# MCU.net
KiCad netlist of a schematic drawn in Altium Designer
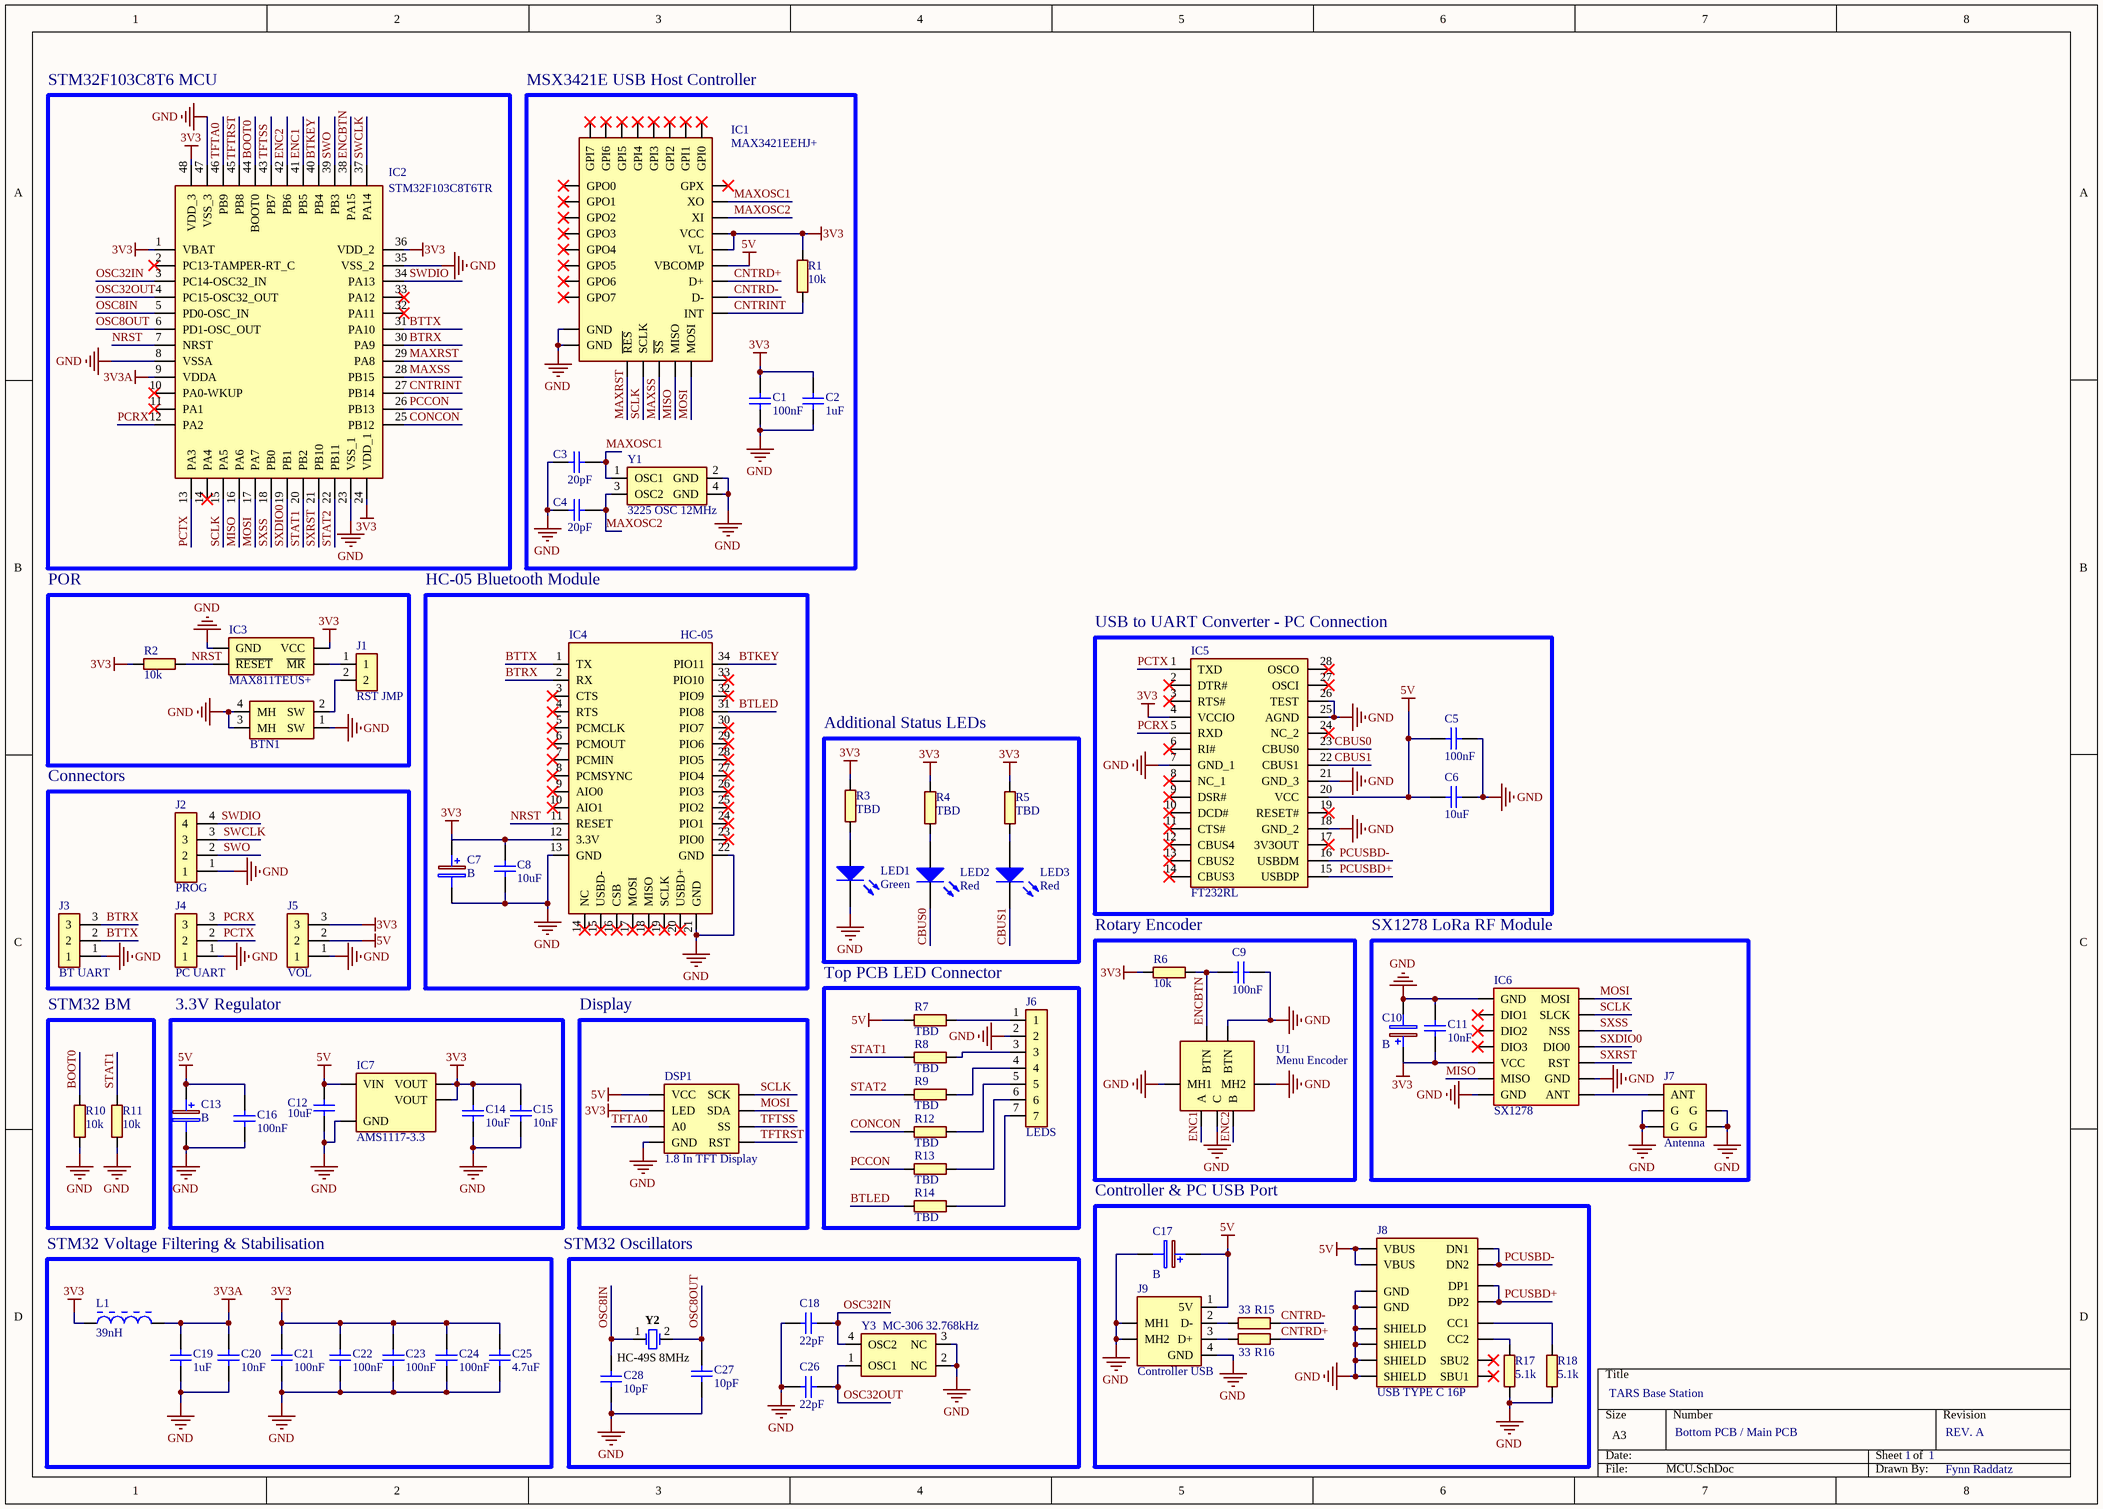
[diagram p0: MCU.SchDoc]

(export (version "E")
  (design (tool "Eeschema 10.0.6"))
  (components
    (comp (ref "BTN1")
      (value "SMD Button 6x6mm Angled")
      (footprint "SMD Button 6x6 Angled")
      (libsource (lib "SamacSys") (part "SMD Button 6x6mm Angled"))
    )
    (comp (ref "C1")
      (value "100nF")
      (footprint "SamacSys:CAPC2012 METRIC")
      (description "Capacitor")
      (fields (field (name "MANUFACTURER_PART_NUMBER") "CL21B104KACNNNC"))
      (libsource (lib "SamacSys") (part "CL21B104KACNNNC"))
    )
    (comp (ref "C2")
      (value "1uF")
      (footprint "SamacSys:CAPC2012 METRIC")
      (description "Capacitor")
      (fields (field (name "MANUFACTURER_PART_NUMBER") "CL21B104KACNNNC"))
      (libsource (lib "SamacSys") (part "CL21B104KACNNNC"))
    )
    (comp (ref "C3")
      (value "20pF")
      (footprint "SamacSys:CAPC2012 METRIC")
      (description "Capacitor")
      (fields (field (name "MANUFACTURER_PART_NUMBER") "CL21B104KACNNNC"))
      (libsource (lib "SamacSys") (part "CL21B104KACNNNC"))
    )
    (comp (ref "C4")
      (value "20pF")
      (footprint "SamacSys:CAPC2012 METRIC")
      (description "Capacitor")
      (fields (field (name "MANUFACTURER_PART_NUMBER") "CL21B104KACNNNC"))
      (libsource (lib "SamacSys") (part "CL21B104KACNNNC"))
    )
    (comp (ref "C5")
      (value "100nF")
      (footprint "SamacSys:CAPC2012 METRIC")
      (description "Capacitor")
      (fields (field (name "MANUFACTURER_PART_NUMBER") "CL21B104KACNNNC"))
      (libsource (lib "SamacSys") (part "CL21B104KACNNNC"))
    )
    (comp (ref "C6")
      (value "10uF")
      (footprint "SamacSys:CAPC2012 METRIC")
      (description "Capacitor")
      (fields (field (name "MANUFACTURER_PART_NUMBER") "CL21B104KACNNNC"))
      (libsource (lib "SamacSys") (part "CL21B104KACNNNC"))
    )
    (comp (ref "C7")
      (value "B")
      (footprint "Tantal-B-1210")
      (description "Capacitor Tantalum")
      (libsource (lib "SamacSys") (part "TANTAL-B"))
    )
    (comp (ref "C8")
      (value "10uF")
      (footprint "SamacSys:CAPC2012 METRIC")
      (description "Capacitor")
      (fields (field (name "MANUFACTURER_PART_NUMBER") "CL21B104KACNNNC"))
      (libsource (lib "SamacSys") (part "CL21B104KACNNNC"))
    )
    (comp (ref "C9")
      (value "100nF")
      (footprint "SamacSys:CAPC2012 METRIC")
      (description "Capacitor")
      (fields (field (name "MANUFACTURER_PART_NUMBER") "CL21B104KACNNNC"))
      (libsource (lib "SamacSys") (part "CL21B104KACNNNC"))
    )
    (comp (ref "C10")
      (value "B")
      (footprint "Tantal-B-1210")
      (description "Capacitor Tantalum")
      (libsource (lib "") (part "TANTAL-B_1"))
    )
    (comp (ref "C11")
      (value "10nF")
      (footprint "SamacSys:CAPC2012 METRIC")
      (description "Capacitor")
      (fields (field (name "MANUFACTURER_PART_NUMBER") "CL21B104KACNNNC"))
      (libsource (lib "SamacSys") (part "CL21B104KACNNNC"))
    )
    (comp (ref "C12")
      (value "10uF")
      (footprint "SamacSys:CAPC2012 METRIC")
      (description "Capacitor")
      (fields (field (name "MANUFACTURER_PART_NUMBER") "CL21B104KACNNNC"))
      (libsource (lib "SamacSys") (part "CL21B104KACNNNC"))
    )
    (comp (ref "C13")
      (value "B")
      (footprint "Tantal-B-1210")
      (description "Capacitor Tantalum")
      (libsource (lib "SamacSys") (part "TANTAL-B"))
    )
    (comp (ref "C14")
      (value "10uF")
      (footprint "SamacSys:CAPC2012 METRIC")
      (description "Capacitor")
      (fields (field (name "MANUFACTURER_PART_NUMBER") "CL21B104KACNNNC"))
      (libsource (lib "SamacSys") (part "CL21B104KACNNNC"))
    )
    (comp (ref "C15")
      (value "10nF")
      (footprint "SamacSys:CAPC2012 METRIC")
      (description "Capacitor")
      (fields (field (name "MANUFACTURER_PART_NUMBER") "CL21B104KACNNNC"))
      (libsource (lib "SamacSys") (part "CL21B104KACNNNC"))
    )
    (comp (ref "C16")
      (value "100nF")
      (footprint "SamacSys:CAPC2012 METRIC")
      (description "Capacitor")
      (fields (field (name "MANUFACTURER_PART_NUMBER") "CL21B104KACNNNC"))
      (libsource (lib "SamacSys") (part "CL21B104KACNNNC"))
    )
    (comp (ref "C17")
      (value "B")
      (footprint "Tantal-B-1210")
      (description "Capacitor Tantalum")
      (libsource (lib "") (part "TANTAL-B_2"))
    )
    (comp (ref "C18")
      (value "22pF")
      (footprint "SamacSys:CAPC2012 METRIC")
      (description "Capacitor")
      (fields (field (name "MANUFACTURER_PART_NUMBER") "CL21B104KACNNNC"))
      (libsource (lib "SamacSys") (part "CL21B104KACNNNC"))
    )
    (comp (ref "C19")
      (value "1uF")
      (footprint "SamacSys:CAPC2012 METRIC")
      (description "Capacitor")
      (fields (field (name "MANUFACTURER_PART_NUMBER") "CL21B104KACNNNC"))
      (libsource (lib "SamacSys") (part "CL21B104KACNNNC"))
    )
    (comp (ref "C20")
      (value "10nF")
      (footprint "SamacSys:CAPC2012 METRIC")
      (description "Capacitor")
      (fields (field (name "MANUFACTURER_PART_NUMBER") "CL21B104KACNNNC"))
      (libsource (lib "SamacSys") (part "CL21B104KACNNNC"))
    )
    (comp (ref "C21")
      (value "100nF")
      (footprint "SamacSys:CAPC2012 METRIC")
      (description "Capacitor")
      (fields (field (name "MANUFACTURER_PART_NUMBER") "CL21B104KACNNNC"))
      (libsource (lib "SamacSys") (part "CL21B104KACNNNC"))
    )
    (comp (ref "C22")
      (value "100nF")
      (footprint "SamacSys:CAPC2012 METRIC")
      (description "Capacitor")
      (fields (field (name "MANUFACTURER_PART_NUMBER") "CL21B104KACNNNC"))
      (libsource (lib "SamacSys") (part "CL21B104KACNNNC"))
    )
    (comp (ref "C23")
      (value "100nF")
      (footprint "SamacSys:CAPC2012 METRIC")
      (description "Capacitor")
      (fields (field (name "MANUFACTURER_PART_NUMBER") "CL21B104KACNNNC"))
      (libsource (lib "SamacSys") (part "CL21B104KACNNNC"))
    )
    (comp (ref "C24")
      (value "100nF")
      (footprint "SamacSys:CAPC2012 METRIC")
      (description "Capacitor")
      (fields (field (name "MANUFACTURER_PART_NUMBER") "CL21B104KACNNNC"))
      (libsource (lib "SamacSys") (part "CL21B104KACNNNC"))
    )
    (comp (ref "C25")
      (value "4.7uF")
      (footprint "SamacSys:CAPC2012 METRIC")
      (description "Capacitor")
      (fields (field (name "MANUFACTURER_PART_NUMBER") "CL21B104KACNNNC"))
      (libsource (lib "SamacSys") (part "CL21B104KACNNNC"))
    )
    (comp (ref "C26")
      (value "22pF")
      (footprint "SamacSys:CAPC2012 METRIC")
      (description "Capacitor")
      (fields (field (name "MANUFACTURER_PART_NUMBER") "CL21B104KACNNNC"))
      (libsource (lib "SamacSys") (part "CL21B104KACNNNC"))
    )
    (comp (ref "C27")
      (value "10pF")
      (footprint "SamacSys:CAPC2012 METRIC")
      (description "Capacitor")
      (fields (field (name "MANUFACTURER_PART_NUMBER") "CL21B104KACNNNC"))
      (libsource (lib "SamacSys") (part "CL21B104KACNNNC"))
    )
    (comp (ref "C28")
      (value "10pF")
      (footprint "SamacSys:CAPC2012 METRIC")
      (description "Capacitor")
      (fields (field (name "MANUFACTURER_PART_NUMBER") "CL21B104KACNNNC"))
      (libsource (lib "SamacSys") (part "CL21B104KACNNNC"))
    )
    (comp (ref "DSP1")
      (value "1.8 In TFT Display")
      (footprint "1.8 Inch TFT Display")
      (description "Display")
      (libsource (lib "SamacSys") (part "TFT Display 1.8In SPI"))
    )
    (comp (ref "IC1")
      (value "MAX3421EEHJ+")
      (footprint "SamacSys:QFP50P700X700X120-32N")
      (description "Integrated Circuit")
      (fields (field (name "MOUSER PART NUMBER") "700-MAX3421EEHJ"))
      (libsource (lib "SamacSys") (part "MAX3421EEHJ+"))
    )
    (comp (ref "IC2")
      (value "STM32F103C8T6TR")
      (footprint "SamacSys:QFP50P900X900X160-48N")
      (description "Integrated Circuit")
      (fields (field (name "MOUSER PART NUMBER") "511-STM32F103C8T6TR"))
      (libsource (lib "SamacSys") (part "STM32F103C8T6TR"))
    )
    (comp (ref "IC3")
      (value "MAX811TEUS+")
      (footprint "SamacSys:MAX811REUST")
      (description "Integrated Circuit")
      (libsource (lib "SamacSys") (part "MAX811TEUS+"))
    )
    (comp (ref "IC4") (value "HC-05") (footprint "HC-05") (libsource (lib "SamacSys") (part "HC-05")))
    (comp (ref "IC5")
      (value "FT232RL")
      (footprint "SamacSys:SOP65P778X200-28N")
      (description "Integrated Circuit")
      (libsource (lib "SamacSys") (part "FT232RL"))
    )
    (comp (ref "IC6")
      (value "SX1278")
      (footprint "SamacSys:SX1278")
      (description "RF")
      (libsource (lib "SamacSys") (part "SX1278"))
    )
    (comp (ref "IC7")
      (value "AMS1117-3.3")
      (footprint "SamacSys:SOT229P700X180-4N")
      (description "Integrated Circuit")
      (libsource (lib "SamacSys") (part "AMS1117-3.3"))
    )
    (comp (ref "J1")
      (value "RST JMP")
      (footprint "SamacSys:HDRV2W110P0X254_1X2_508X254X854P")
      (description "Connector")
      (fields
        (field (name "MANUFACTURER_PART_NUMBER") "61300211121")
        (field (name "MOUSER PART NUMBER") "710-61300211121")
      )
      (libsource (lib "SamacSys") (part "61300211121"))
    )
    (comp (ref "J2")
      (value "PROG")
      (footprint "SamacSys:HDRV4W95P0X254_1X4_1016X254X854P")
      (description "Connector")
      (fields
        (field (name "MANUFACTURER_PART_NUMBER") "61300411121")
        (field (name "MOUSER PART NUMBER") "710-61300411121")
      )
      (libsource (lib "SamacSys") (part "61300411121"))
    )
    (comp (ref "J3")
      (value "BT UART")
      (footprint "SamacSys:HDRV3W64P0X254_1X3_762X254X869P")
      (description "Connector")
      (fields
        (field (name "MANUFACTURER_PART_NUMBER") "61300311121")
        (field (name "MOUSER PART NUMBER") "710-61300311121")
      )
      (libsource (lib "SamacSys") (part "61300311121"))
    )
    (comp (ref "J4")
      (value "PC UART")
      (footprint "SamacSys:HDRV3W64P0X254_1X3_762X254X869P")
      (description "Connector")
      (fields
        (field (name "MANUFACTURER_PART_NUMBER") "61300311121")
        (field (name "MOUSER PART NUMBER") "710-61300311121")
      )
      (libsource (lib "SamacSys") (part "61300311121"))
    )
    (comp (ref "J5")
      (value "VOL")
      (footprint "SamacSys:HDRV3W64P0X254_1X3_762X254X869P")
      (description "Connector")
      (fields
        (field (name "MANUFACTURER_PART_NUMBER") "61300311121")
        (field (name "MOUSER PART NUMBER") "710-61300311121")
      )
      (libsource (lib "SamacSys") (part "61300311121"))
    )
    (comp (ref "J6")
      (value "LEDS")
      (footprint "SamacSys:HDRV7W64P0X254_1X7_1778X254X869P")
      (description "Connector")
      (fields
        (field (name "MANUFACTURER_PART_NUMBER") "61300711121")
        (field (name "MOUSER PART NUMBER") "710-61300711121")
      )
      (libsource (lib "SamacSys") (part "61300711121"))
    )
    (comp (ref "J7")
      (value "Antenna")
      (footprint "SamacSys:PCBRPSMAFRAHT")
      (description "Connector")
      (fields
        (field (name "MANUFACTURER_PART_NUMBER") "PCB.RPSMAFRA.HT")
        (field (name "MOUSER PART NUMBER") "960-PCB.RPSMAFRA.HT")
      )
      (libsource (lib "SamacSys") (part "PCB.RPSMAFRA.HT"))
    )
    (comp (ref "J8")
      (value "USB TYPE C 16P")
      (footprint "USB TYPE C 16P")
      (libsource (lib "SamacSys") (part "USB TYPE C 16P"))
    )
    (comp (ref "J9")
      (value "Controller USB")
      (footprint "SamacSys:875200010BLF")
      (description "Connector")
      (fields
        (field (name "MANUFACTURER_PART_NUMBER") "87520-0010BLF")
        (field (name "MOUSER PART NUMBER") "649-87520-0010BLF")
      )
      (libsource (lib "SamacSys") (part "87520-0010BLF"))
    )
    (comp (ref "L1")
      (value "39nH")
      (footprint "LIRD-LI0805H151R-10-2_V")
      (description "Chip Bead, 100 MHz, 5 A, -40 to 125 degC, 2-Pin SMD (0805), RoHS, Tape and Reel")
      (fields (field (name "MANUFACTURER") "Laird"))
      (libsource (lib "Altium Content Vault") (part "IND-FB-2"))
    )
    (comp (ref "LED1")
      (value "Green")
      (footprint "1206_A")
      (description "SMD mono-color Chip LED, WL-SMCW, Green")
      (fields (field (name "MANUFACTURER") "Wuerth Elektronik") (field (name "PARTNUMBER") "150120GS75000"))
      (libsource (lib "Altium Content Vault") (part "WE-LED_K1A2-2"))
    )
    (comp (ref "LED2")
      (value "Red")
      (footprint "1206_A")
      (description "SMD mono-color Chip LED, WL-SMCW, Green")
      (fields (field (name "MANUFACTURER") "Wuerth Elektronik") (field (name "PARTNUMBER") "150120GS75000"))
      (libsource (lib "Altium Content Vault") (part "WE-LED_K1A2-2"))
    )
    (comp (ref "LED3")
      (value "Red")
      (footprint "1206_A")
      (description "SMD mono-color Chip LED, WL-SMCW, Green")
      (fields (field (name "MANUFACTURER") "Wuerth Elektronik") (field (name "PARTNUMBER") "150120GS75000"))
      (libsource (lib "Altium Content Vault") (part "WE-LED_K1A2-2"))
    )
    (comp (ref "R1")
      (value "10k")
      (footprint "SamacSys:RESC2012X65N")
      (description "Resistor")
      (fields (field (name "MANUFACTURER_PART_NUMBER") "RMCF0805ZT0R00"))
      (libsource (lib "SamacSys") (part "Res 0805"))
    )
    (comp (ref "R2")
      (value "10k")
      (footprint "SamacSys:RESC2012X65N")
      (description "Resistor")
      (fields (field (name "MANUFACTURER_PART_NUMBER") "RMCF0805ZT0R00"))
      (libsource (lib "") (part "Res 0805_1"))
    )
    (comp (ref "R3")
      (value "TBD")
      (footprint "SamacSys:RESC2012X65N")
      (description "Resistor")
      (fields (field (name "MANUFACTURER_PART_NUMBER") "RMCF0805ZT0R00"))
      (libsource (lib "SamacSys") (part "Res 0805"))
    )
    (comp (ref "R4")
      (value "TBD")
      (footprint "SamacSys:RESC2012X65N")
      (description "Resistor")
      (fields (field (name "MANUFACTURER_PART_NUMBER") "RMCF0805ZT0R00"))
      (libsource (lib "SamacSys") (part "Res 0805"))
    )
    (comp (ref "R5")
      (value "TBD")
      (footprint "SamacSys:RESC2012X65N")
      (description "Resistor")
      (fields (field (name "MANUFACTURER_PART_NUMBER") "RMCF0805ZT0R00"))
      (libsource (lib "SamacSys") (part "Res 0805"))
    )
    (comp (ref "R6")
      (value "10k")
      (footprint "SamacSys:RESC2012X65N")
      (description "Resistor")
      (fields (field (name "MANUFACTURER_PART_NUMBER") "RMCF0805ZT0R00"))
      (libsource (lib "") (part "Res 0805_1"))
    )
    (comp (ref "R7")
      (value "TBD")
      (footprint "SamacSys:RESC2012X65N")
      (description "Resistor")
      (fields (field (name "MANUFACTURER_PART_NUMBER") "RMCF0805ZT0R00"))
      (libsource (lib "") (part "Res 0805_1"))
    )
    (comp (ref "R8")
      (value "TBD")
      (footprint "SamacSys:RESC2012X65N")
      (description "Resistor")
      (fields (field (name "MANUFACTURER_PART_NUMBER") "RMCF0805ZT0R00"))
      (libsource (lib "") (part "Res 0805_1"))
    )
    (comp (ref "R9")
      (value "TBD")
      (footprint "SamacSys:RESC2012X65N")
      (description "Resistor")
      (fields (field (name "MANUFACTURER_PART_NUMBER") "RMCF0805ZT0R00"))
      (libsource (lib "") (part "Res 0805_1"))
    )
    (comp (ref "R10")
      (value "10k")
      (footprint "SamacSys:RESC2012X65N")
      (description "Resistor")
      (fields (field (name "MANUFACTURER_PART_NUMBER") "RMCF0805ZT0R00"))
      (libsource (lib "") (part "Res 0805_3"))
    )
    (comp (ref "R11")
      (value "10k")
      (footprint "SamacSys:RESC2012X65N")
      (description "Resistor")
      (fields (field (name "MANUFACTURER_PART_NUMBER") "RMCF0805ZT0R00"))
      (libsource (lib "") (part "Res 0805_3"))
    )
    (comp (ref "R12")
      (value "TBD")
      (footprint "SamacSys:RESC2012X65N")
      (description "Resistor")
      (fields (field (name "MANUFACTURER_PART_NUMBER") "RMCF0805ZT0R00"))
      (libsource (lib "") (part "Res 0805_1"))
    )
    (comp (ref "R13")
      (value "TBD")
      (footprint "SamacSys:RESC2012X65N")
      (description "Resistor")
      (fields (field (name "MANUFACTURER_PART_NUMBER") "RMCF0805ZT0R00"))
      (libsource (lib "") (part "Res 0805_1"))
    )
    (comp (ref "R14")
      (value "TBD")
      (footprint "SamacSys:RESC2012X65N")
      (description "Resistor")
      (fields (field (name "MANUFACTURER_PART_NUMBER") "RMCF0805ZT0R00"))
      (libsource (lib "") (part "Res 0805_1"))
    )
    (comp (ref "R15")
      (value "33")
      (footprint "SamacSys:RESC2012X65N")
      (description "Resistor")
      (fields (field (name "MANUFACTURER_PART_NUMBER") "RMCF0805ZT0R00"))
      (libsource (lib "") (part "Res 0805_2"))
    )
    (comp (ref "R16")
      (value "33")
      (footprint "SamacSys:RESC2012X65N")
      (description "Resistor")
      (fields (field (name "MANUFACTURER_PART_NUMBER") "RMCF0805ZT0R00"))
      (libsource (lib "") (part "Res 0805_2"))
    )
    (comp (ref "R17")
      (value "5.1k")
      (footprint "SamacSys:RESC2012X65N")
      (description "Resistor")
      (fields (field (name "MANUFACTURER_PART_NUMBER") "RMCF0805ZT0R00"))
      (libsource (lib "SamacSys") (part "Res 0805"))
    )
    (comp (ref "R18")
      (value "5.1k")
      (footprint "SamacSys:RESC2012X65N")
      (description "Resistor")
      (fields (field (name "MANUFACTURER_PART_NUMBER") "RMCF0805ZT0R00"))
      (libsource (lib "SamacSys") (part "Res 0805"))
    )
    (comp (ref "U1")
      (value "Menu Encoder")
      (footprint "SamacSys:EC11B152442D")
      (description "Encoder")
      (fields (field (name "MANUFACTURER_PART_NUMBER") "EC11B152442D"))
      (libsource (lib "SamacSys") (part "EC11B152442D"))
    )
    (comp (ref "Y1")
      (value "3225 OSC 12MHz")
      (footprint "SamacSys:TSX3225240000MF20GAC0")
      (description "Crystal or Oscillator")
      (fields
        (field (name "MANUFACTURER_PART_NUMBER") "TSX-3225 16.0000MF10U-B0")
        (field (name "MOUSER PART NUMBER") "732-322516MF10U-B0")
      )
      (libsource (lib "SamacSys") (part "TSX-3225_16.0000MF10U-B0"))
    )
    (comp (ref "Y2")
      (value "HC-49S 8MHz")
      (footprint "FOX-HC49SDLF_V")
      (description "Resistance Weld Crystal, 8 MHz, +/- 30 ppm, -20 to 70 degC, 2-Pin SMD, RoHS, Tape and Reel")
      (fields (field (name "MANUFACTURER") "FOX Electronics") (field (name "TOLERANCE") "50ppm"))
      (libsource (lib "Altium Content Vault") (part "XTAL-1-2-2"))
    )
    (comp (ref "Y3")
      (value "MC-306 32.768kHz")
      (footprint "SamacSys:MC306327680KA3ROHS")
      (description "Crystal or Oscillator")
      (fields
        (field (name "MANUFACTURER_PART_NUMBER") "MC-306 32.7680K-A3:ROHS")
        (field (name "MOUSER PART NUMBER") "732-MC306-32.7KA3R")
      )
      (libsource (lib "SamacSys") (part "MC-306_32.7680K-A3_ROHS"))
    )
  )
  (nets
    (net (code "1") (name "/BOOT0") (class "Default")
      (node (ref "IC2") (pin "44") (pinfunction "BOOT0_44") (pintype "passive"))
      (node (ref "R10") (pin "1") (pinfunction "1_1") (pintype "passive"))
    )
    (net (code "2") (name "/BTKEY") (class "Default")
      (node (ref "IC2") (pin "40") (pinfunction "PB4_40") (pintype "passive"))
      (node (ref "IC4") (pin "34") (pinfunction "PIO11_34") (pintype "passive"))
    )
    (net (code "3") (name "/BTLED") (class "Default")
      (node (ref "IC4") (pin "31") (pinfunction "PIO8_31") (pintype "passive"))
      (node (ref "R14") (pin "2") (pinfunction "2_2") (pintype "passive"))
    )
    (net (code "4") (name "/BTRX") (class "Default")
      (node (ref "IC2") (pin "30") (pinfunction "PA9_30") (pintype "passive"))
      (node (ref "IC4") (pin "2") (pinfunction "RX_2") (pintype "passive"))
      (node (ref "J3") (pin "3") (pinfunction "3_3") (pintype "passive"))
    )
    (net (code "5") (name "/BTTX") (class "Default")
      (node (ref "IC2") (pin "31") (pinfunction "PA10_31") (pintype "passive"))
      (node (ref "IC4") (pin "1") (pinfunction "TX_1") (pintype "passive"))
      (node (ref "J3") (pin "2") (pinfunction "2_2") (pintype "passive"))
    )
    (net (code "6") (name "/CBUS0") (class "Default")
      (node (ref "IC5") (pin "23") (pinfunction "CBUS0_23") (pintype "passive"))
      (node (ref "LED2") (pin "1") (pinfunction "K_1") (pintype "passive"))
    )
    (net (code "7") (name "/CBUS1") (class "Default")
      (node (ref "IC5") (pin "22") (pinfunction "CBUS1_22") (pintype "passive"))
      (node (ref "LED3") (pin "1") (pinfunction "K_1") (pintype "passive"))
    )
    (net (code "8") (name "/CNTRD+") (class "Default")
      (node (ref "IC1") (pin "21") (pinfunction "D+_21") (pintype "passive"))
      (node (ref "R16") (pin "2") (pinfunction "2_2") (pintype "passive"))
    )
    (net (code "9") (name "/CNTRD-") (class "Default")
      (node (ref "IC1") (pin "20") (pinfunction "D-_20") (pintype "passive"))
      (node (ref "R15") (pin "2") (pinfunction "2_2") (pintype "passive"))
    )
    (net (code "10") (name "/CNTRINT") (class "Default")
      (node (ref "IC1") (pin "18") (pinfunction "INT_18") (pintype "passive"))
      (node (ref "IC2") (pin "27") (pinfunction "PB14_27") (pintype "passive"))
      (node (ref "R1") (pin "1") (pinfunction "1_1") (pintype "passive"))
    )
    (net (code "11") (name "/CONCON") (class "Default")
      (node (ref "IC2") (pin "25") (pinfunction "PB12_25") (pintype "passive"))
      (node (ref "R12") (pin "2") (pinfunction "2_2") (pintype "passive"))
    )
    (net (code "12") (name "/ENC1") (class "Default")
      (node (ref "IC2") (pin "41") (pinfunction "PB5_41") (pintype "passive"))
      (node (ref "U1") (pin "A") (pinfunction "A_A") (pintype "passive"))
    )
    (net (code "13") (name "/ENC2") (class "Default")
      (node (ref "IC2") (pin "42") (pinfunction "PB6_42") (pintype "passive"))
      (node (ref "U1") (pin "B") (pinfunction "B_B") (pintype "passive"))
    )
    (net (code "14") (name "/ENCBTN") (class "Default")
      (node (ref "C9") (pin "1") (pinfunction "1_1") (pintype "passive"))
      (node (ref "IC2") (pin "38") (pinfunction "PA15_38") (pintype "passive"))
      (node (ref "R6") (pin "1") (pinfunction "1_1") (pintype "passive"))
      (node (ref "U1") (pin "MH3") (pinfunction "BTN_MH3") (pintype "passive"))
    )
    (net (code "15") (name "/MAXOSC1") (class "Default")
      (node (ref "C3") (pin "1") (pinfunction "1_1") (pintype "passive"))
      (node (ref "IC1") (pin "25") (pinfunction "XO_25") (pintype "passive"))
      (node (ref "Y1") (pin "1") (pinfunction "OSC1_1") (pintype "passive"))
    )
    (net (code "16") (name "/MAXOSC2") (class "Default")
      (node (ref "C4") (pin "1") (pinfunction "1_1") (pintype "passive"))
      (node (ref "IC1") (pin "24") (pinfunction "XI_24") (pintype "passive"))
      (node (ref "Y1") (pin "3") (pinfunction "OSC2_3") (pintype "passive"))
    )
    (net (code "17") (name "/MAXRST") (class "Default")
      (node (ref "IC1") (pin "12") (pinfunction "~{RES}_12") (pintype "passive"))
      (node (ref "IC2") (pin "29") (pinfunction "PA8_29") (pintype "passive"))
    )
    (net (code "18") (name "/MAXSS") (class "Default")
      (node (ref "IC1") (pin "14") (pinfunction "~{SS}_14") (pintype "passive"))
      (node (ref "IC2") (pin "28") (pinfunction "PB15_28") (pintype "passive"))
    )
    (net (code "19") (name "/MISO") (class "Default")
      (node (ref "IC1") (pin "15") (pinfunction "MISO_15") (pintype "passive"))
      (node (ref "IC2") (pin "16") (pinfunction "PA6_16") (pintype "passive"))
      (node (ref "IC6") (pin "6") (pinfunction "MISO_6") (pintype "passive"))
    )
    (net (code "20") (name "/MOSI") (class "Default")
      (node (ref "DSP1") (pin "3") (pinfunction "SDA_3") (pintype "passive"))
      (node (ref "IC1") (pin "16") (pinfunction "MOSI_16") (pintype "passive"))
      (node (ref "IC2") (pin "17") (pinfunction "PA7_17") (pintype "passive"))
      (node (ref "IC6") (pin "7") (pinfunction "MOSI_7") (pintype "passive"))
    )
    (net (code "21") (name "/NRST") (class "Default")
      (node (ref "IC2") (pin "7") (pinfunction "NRST_7") (pintype "passive"))
      (node (ref "IC3") (pin "2") (pinfunction "~{RESET}_2") (pintype "passive"))
      (node (ref "IC4") (pin "11") (pinfunction "RESET_11") (pintype "passive"))
      (node (ref "R2") (pin "1") (pinfunction "1_1") (pintype "passive"))
    )
    (net (code "22") (name "/OSC8IN") (class "Default")
      (node (ref "C28") (pin "2") (pinfunction "2_2") (pintype "passive"))
      (node (ref "IC2") (pin "5") (pinfunction "PD0-OSC_IN_5") (pintype "passive"))
      (node (ref "Y2") (pin "1") (pinfunction "1_1") (pintype "passive"))
    )
    (net (code "23") (name "/OSC8OUT") (class "Default")
      (node (ref "C27") (pin "2") (pinfunction "2_2") (pintype "passive"))
      (node (ref "IC2") (pin "6") (pinfunction "PD1-OSC_OUT_6") (pintype "passive"))
      (node (ref "Y2") (pin "2") (pinfunction "2_2") (pintype "passive"))
    )
    (net (code "24") (name "/OSC32IN") (class "Default")
      (node (ref "C18") (pin "1") (pinfunction "1_1") (pintype "passive"))
      (node (ref "IC2") (pin "3") (pinfunction "PC14-OSC32_IN_3") (pintype "passive"))
      (node (ref "Y3") (pin "4") (pinfunction "OSC2_4") (pintype "passive"))
    )
    (net (code "25") (name "/OSC32OUT") (class "Default")
      (node (ref "C26") (pin "1") (pinfunction "1_1") (pintype "passive"))
      (node (ref "IC2") (pin "4") (pinfunction "PC15-OSC32_OUT_4") (pintype "passive"))
      (node (ref "Y3") (pin "1") (pinfunction "OSC1_1") (pintype "passive"))
    )
    (net (code "26") (name "/PCCON") (class "Default")
      (node (ref "IC2") (pin "26") (pinfunction "PB13_26") (pintype "passive"))
      (node (ref "R13") (pin "2") (pinfunction "2_2") (pintype "passive"))
    )
    (net (code "27") (name "/PCRX") (class "Default")
      (node (ref "IC2") (pin "12") (pinfunction "PA2_12") (pintype "passive"))
      (node (ref "IC5") (pin "5") (pinfunction "RXD_5") (pintype "passive"))
      (node (ref "J4") (pin "3") (pinfunction "3_3") (pintype "passive"))
    )
    (net (code "28") (name "/PCTX") (class "Default")
      (node (ref "IC2") (pin "13") (pinfunction "PA3_13") (pintype "passive"))
      (node (ref "IC5") (pin "1") (pinfunction "TXD_1") (pintype "passive"))
      (node (ref "J4") (pin "2") (pinfunction "2_2") (pintype "passive"))
    )
    (net (code "29") (name "/PCUSBD+") (class "Default")
      (node (ref "IC5") (pin "15") (pinfunction "USBDP_15") (pintype "passive"))
      (node (ref "J8") (pin "A6") (pinfunction "DP1_A6") (pintype "passive"))
      (node (ref "J8") (pin "B6") (pinfunction "DP2_B6") (pintype "passive"))
    )
    (net (code "30") (name "/PCUSBD-") (class "Default")
      (node (ref "IC5") (pin "16") (pinfunction "USBDM_16") (pintype "passive"))
      (node (ref "J8") (pin "A7") (pinfunction "DN1_A7") (pintype "passive"))
      (node (ref "J8") (pin "B7") (pinfunction "DN2_B7") (pintype "passive"))
    )
    (net (code "31") (name "/SCLK") (class "Default")
      (node (ref "DSP1") (pin "2") (pinfunction "SCK_2") (pintype "passive"))
      (node (ref "IC1") (pin "13") (pinfunction "SCLK_13") (pintype "passive"))
      (node (ref "IC2") (pin "15") (pinfunction "PA5_15") (pintype "passive"))
      (node (ref "IC6") (pin "8") (pinfunction "SLCK_8") (pintype "passive"))
    )
    (net (code "32") (name "/STAT1") (class "Default")
      (node (ref "IC2") (pin "20") (pinfunction "PB2_20") (pintype "passive"))
      (node (ref "R11") (pin "1") (pinfunction "1_1") (pintype "passive"))
      (node (ref "R8") (pin "2") (pinfunction "2_2") (pintype "passive"))
    )
    (net (code "33") (name "/STAT2") (class "Default")
      (node (ref "IC2") (pin "22") (pinfunction "PB11_22") (pintype "passive"))
      (node (ref "R9") (pin "2") (pinfunction "2_2") (pintype "passive"))
    )
    (net (code "34") (name "/SWCLK") (class "Default")
      (node (ref "IC2") (pin "37") (pinfunction "PA14_37") (pintype "passive"))
      (node (ref "J2") (pin "3") (pinfunction "3_3") (pintype "passive"))
    )
    (net (code "35") (name "/SWDIO") (class "Default")
      (node (ref "IC2") (pin "34") (pinfunction "PA13_34") (pintype "passive"))
      (node (ref "J2") (pin "4") (pinfunction "4_4") (pintype "passive"))
    )
    (net (code "36") (name "/SWO") (class "Default")
      (node (ref "IC2") (pin "39") (pinfunction "PB3_39") (pintype "passive"))
      (node (ref "J2") (pin "2") (pinfunction "2_2") (pintype "passive"))
    )
    (net (code "37") (name "/SXDIO0") (class "Default")
      (node (ref "IC2") (pin "19") (pinfunction "PB1_19") (pintype "passive"))
      (node (ref "IC6") (pin "10") (pinfunction "DIO0_10") (pintype "passive"))
    )
    (net (code "38") (name "/SXRST") (class "Default")
      (node (ref "IC2") (pin "21") (pinfunction "PB10_21") (pintype "passive"))
      (node (ref "IC6") (pin "11") (pinfunction "RST_11") (pintype "passive"))
    )
    (net (code "39") (name "/SXSS") (class "Default")
      (node (ref "IC2") (pin "18") (pinfunction "PB0_18") (pintype "passive"))
      (node (ref "IC6") (pin "9") (pinfunction "NSS_9") (pintype "passive"))
    )
    (net (code "40") (name "/TFTA0") (class "Default")
      (node (ref "DSP1") (pin "4") (pinfunction "A0_4") (pintype "passive"))
      (node (ref "IC2") (pin "46") (pinfunction "PB9_46") (pintype "passive"))
    )
    (net (code "41") (name "/TFTRST") (class "Default")
      (node (ref "DSP1") (pin "5") (pinfunction "RST_5") (pintype "passive"))
      (node (ref "IC2") (pin "45") (pinfunction "PB8_45") (pintype "passive"))
    )
    (net (code "42") (name "/TFTSS") (class "Default")
      (node (ref "DSP1") (pin "6") (pinfunction "SS_6") (pintype "passive"))
      (node (ref "IC2") (pin "43") (pinfunction "PB7_43") (pintype "passive"))
    )
    (net (code "43") (name "3V3") (class "Default")
      (node (ref "C1") (pin "1") (pinfunction "1_1") (pintype "passive"))
      (node (ref "C10") (pin "1") (pinfunction "+_1") (pintype "passive"))
      (node (ref "C11") (pin "2") (pinfunction "2_2") (pintype "passive"))
      (node (ref "C14") (pin "1") (pinfunction "1_1") (pintype "passive"))
      (node (ref "C15") (pin "1") (pinfunction "1_1") (pintype "passive"))
      (node (ref "C2") (pin "1") (pinfunction "1_1") (pintype "passive"))
      (node (ref "C21") (pin "2") (pinfunction "2_2") (pintype "passive"))
      (node (ref "C22") (pin "2") (pinfunction "2_2") (pintype "passive"))
      (node (ref "C23") (pin "2") (pinfunction "2_2") (pintype "passive"))
      (node (ref "C24") (pin "2") (pinfunction "2_2") (pintype "passive"))
      (node (ref "C25") (pin "2") (pinfunction "2_2") (pintype "passive"))
      (node (ref "C7") (pin "1") (pinfunction "+_1") (pintype "passive"))
      (node (ref "C8") (pin "1") (pinfunction "1_1") (pintype "passive"))
      (node (ref "DSP1") (pin "1") (pinfunction "LED_1") (pintype "passive"))
      (node (ref "IC1") (pin "2") (pinfunction "VL_2") (pintype "passive"))
      (node (ref "IC1") (pin "23") (pinfunction "VCC_23") (pintype "passive"))
      (node (ref "IC2") (pin "1") (pinfunction "VBAT_1") (pintype "passive"))
      (node (ref "IC2") (pin "24") (pinfunction "VDD_1_24") (pintype "passive"))
      (node (ref "IC2") (pin "36") (pinfunction "VDD_2_36") (pintype "passive"))
      (node (ref "IC2") (pin "48") (pinfunction "VDD_3_48") (pintype "passive"))
      (node (ref "IC3") (pin "4") (pinfunction "VCC_4") (pintype "passive"))
      (node (ref "IC4") (pin "12") (pinfunction "3.3V_12") (pintype "passive"))
      (node (ref "IC5") (pin "4") (pinfunction "VCCIO_4") (pintype "passive"))
      (node (ref "IC6") (pin "5") (pinfunction "VCC_5") (pintype "passive"))
      (node (ref "IC7") (pin "2") (pinfunction "VOUT_2") (pintype "passive"))
      (node (ref "IC7") (pin "4") (pinfunction "VOUT_4") (pintype "passive"))
      (node (ref "J5") (pin "3") (pinfunction "3_3") (pintype "passive"))
      (node (ref "L1") (pin "1") (pinfunction "1_1") (pintype "passive"))
      (node (ref "R1") (pin "2") (pinfunction "2_2") (pintype "passive"))
      (node (ref "R2") (pin "2") (pinfunction "2_2") (pintype "passive"))
      (node (ref "R3") (pin "2") (pinfunction "2_2") (pintype "passive"))
      (node (ref "R4") (pin "2") (pinfunction "2_2") (pintype "passive"))
      (node (ref "R5") (pin "2") (pinfunction "2_2") (pintype "passive"))
      (node (ref "R6") (pin "2") (pinfunction "2_2") (pintype "passive"))
    )
    (net (code "44") (name "3V3A") (class "Default")
      (node (ref "C19") (pin "2") (pinfunction "2_2") (pintype "passive"))
      (node (ref "C20") (pin "2") (pinfunction "2_2") (pintype "passive"))
      (node (ref "IC2") (pin "9") (pinfunction "VDDA_9") (pintype "passive"))
      (node (ref "L1") (pin "2") (pinfunction "2_2") (pintype "passive"))
    )
    (net (code "45") (name "5V") (class "Default")
      (node (ref "C12") (pin "1") (pinfunction "1_1") (pintype "passive"))
      (node (ref "C13") (pin "1") (pinfunction "+_1") (pintype "passive"))
      (node (ref "C16") (pin "2") (pinfunction "2_2") (pintype "passive"))
      (node (ref "C17") (pin "1") (pinfunction "+_1") (pintype "passive"))
      (node (ref "C5") (pin "1") (pinfunction "1_1") (pintype "passive"))
      (node (ref "C6") (pin "1") (pinfunction "1_1") (pintype "passive"))
      (node (ref "DSP1") (pin "8") (pinfunction "VCC_8") (pintype "passive"))
      (node (ref "IC1") (pin "22") (pinfunction "VBCOMP_22") (pintype "passive"))
      (node (ref "IC5") (pin "20") (pinfunction "VCC_20") (pintype "passive"))
      (node (ref "IC7") (pin "3") (pinfunction "VIN_3") (pintype "passive"))
      (node (ref "J5") (pin "2") (pinfunction "2_2") (pintype "passive"))
      (node (ref "J8") (pin "A4B9") (pinfunction "VBUS_A4B9") (pintype "power_in"))
      (node (ref "J8") (pin "B4A9") (pinfunction "VBUS_B4A9") (pintype "power_in"))
      (node (ref "J9") (pin "1") (pinfunction "5V_1") (pintype "passive"))
      (node (ref "R7") (pin "2") (pinfunction "2_2") (pintype "passive"))
    )
    (net (code "46") (name "GND") (class "Default")
      (node (ref "BTN1") (pin "1") (pinfunction "SW_1") (pintype "passive"))
      (node (ref "BTN1") (pin "3") (pinfunction "MH_3") (pintype "passive"))
      (node (ref "BTN1") (pin "4") (pinfunction "MH_4") (pintype "passive"))
      (node (ref "C1") (pin "2") (pinfunction "2_2") (pintype "passive"))
      (node (ref "C10") (pin "2") (pinfunction "-_2") (pintype "passive"))
      (node (ref "C11") (pin "1") (pinfunction "1_1") (pintype "passive"))
      (node (ref "C12") (pin "2") (pinfunction "2_2") (pintype "passive"))
      (node (ref "C13") (pin "2") (pinfunction "-_2") (pintype "passive"))
      (node (ref "C14") (pin "2") (pinfunction "2_2") (pintype "passive"))
      (node (ref "C15") (pin "2") (pinfunction "2_2") (pintype "passive"))
      (node (ref "C16") (pin "1") (pinfunction "1_1") (pintype "passive"))
      (node (ref "C17") (pin "2") (pinfunction "-_2") (pintype "passive"))
      (node (ref "C18") (pin "2") (pinfunction "2_2") (pintype "passive"))
      (node (ref "C19") (pin "1") (pinfunction "1_1") (pintype "passive"))
      (node (ref "C2") (pin "2") (pinfunction "2_2") (pintype "passive"))
      (node (ref "C20") (pin "1") (pinfunction "1_1") (pintype "passive"))
      (node (ref "C21") (pin "1") (pinfunction "1_1") (pintype "passive"))
      (node (ref "C22") (pin "1") (pinfunction "1_1") (pintype "passive"))
      (node (ref "C23") (pin "1") (pinfunction "1_1") (pintype "passive"))
      (node (ref "C24") (pin "1") (pinfunction "1_1") (pintype "passive"))
      (node (ref "C25") (pin "1") (pinfunction "1_1") (pintype "passive"))
      (node (ref "C26") (pin "2") (pinfunction "2_2") (pintype "passive"))
      (node (ref "C27") (pin "1") (pinfunction "1_1") (pintype "passive"))
      (node (ref "C28") (pin "1") (pinfunction "1_1") (pintype "passive"))
      (node (ref "C3") (pin "2") (pinfunction "2_2") (pintype "passive"))
      (node (ref "C4") (pin "2") (pinfunction "2_2") (pintype "passive"))
      (node (ref "C5") (pin "2") (pinfunction "2_2") (pintype "passive"))
      (node (ref "C6") (pin "2") (pinfunction "2_2") (pintype "passive"))
      (node (ref "C7") (pin "2") (pinfunction "-_2") (pintype "passive"))
      (node (ref "C8") (pin "2") (pinfunction "2_2") (pintype "passive"))
      (node (ref "C9") (pin "2") (pinfunction "2_2") (pintype "passive"))
      (node (ref "DSP1") (pin "7") (pinfunction "GND_7") (pintype "passive"))
      (node (ref "IC1") (pin "19") (pinfunction "GND_19") (pintype "passive"))
      (node (ref "IC1") (pin "3") (pinfunction "GND_3") (pintype "passive"))
      (node (ref "IC2") (pin "23") (pinfunction "VSS_1_23") (pintype "passive"))
      (node (ref "IC2") (pin "35") (pinfunction "VSS_2_35") (pintype "passive"))
      (node (ref "IC2") (pin "47") (pinfunction "VSS_3_47") (pintype "passive"))
      (node (ref "IC2") (pin "8") (pinfunction "VSSA_8") (pintype "passive"))
      (node (ref "IC3") (pin "1") (pinfunction "GND_1") (pintype "passive"))
      (node (ref "IC4") (pin "13") (pinfunction "GND_13") (pintype "passive"))
      (node (ref "IC4") (pin "21") (pinfunction "GND_21") (pintype "passive"))
      (node (ref "IC4") (pin "22") (pinfunction "GND_22") (pintype "passive"))
      (node (ref "IC5") (pin "18") (pinfunction "GND_2_18") (pintype "passive"))
      (node (ref "IC5") (pin "21") (pinfunction "GND_3_21") (pintype "passive"))
      (node (ref "IC5") (pin "25") (pinfunction "AGND_25") (pintype "passive"))
      (node (ref "IC5") (pin "26") (pinfunction "TEST_26") (pintype "passive"))
      (node (ref "IC5") (pin "7") (pinfunction "GND_1_7") (pintype "passive"))
      (node (ref "IC6") (pin "1") (pinfunction "GND_1") (pintype "passive"))
      (node (ref "IC6") (pin "12") (pinfunction "GND_12") (pintype "passive"))
      (node (ref "IC6") (pin "14") (pinfunction "GND_14") (pintype "passive"))
      (node (ref "IC7") (pin "1") (pinfunction "GND_1") (pintype "passive"))
      (node (ref "J2") (pin "1") (pinfunction "1_1") (pintype "passive"))
      (node (ref "J3") (pin "1") (pinfunction "1_1") (pintype "passive"))
      (node (ref "J4") (pin "1") (pinfunction "1_1") (pintype "passive"))
      (node (ref "J5") (pin "1") (pinfunction "1_1") (pintype "passive"))
      (node (ref "J6") (pin "2") (pinfunction "2_2") (pintype "passive"))
      (node (ref "J7") (pin "2") (pinfunction "G_2") (pintype "passive"))
      (node (ref "J7") (pin "3") (pinfunction "G_3") (pintype "passive"))
      (node (ref "J7") (pin "4") (pinfunction "G_4") (pintype "passive"))
      (node (ref "J7") (pin "5") (pinfunction "G_5") (pintype "passive"))
      (node (ref "J8") (pin "A1B12") (pinfunction "GND_A1B12") (pintype "power_in"))
      (node (ref "J8") (pin "B1A12") (pinfunction "GND_B1A12") (pintype "power_in"))
      (node (ref "J8") (pin "S1") (pinfunction "SHIELD_S1") (pintype "passive"))
      (node (ref "J8") (pin "S2") (pinfunction "SHIELD_S2") (pintype "passive"))
      (node (ref "J8") (pin "S3") (pinfunction "SHIELD_S3") (pintype "passive"))
      (node (ref "J8") (pin "S4") (pinfunction "SHIELD_S4") (pintype "passive"))
      (node (ref "J9") (pin "4") (pinfunction "GND_4") (pintype "passive"))
      (node (ref "J9") (pin "MH1") (pinfunction "MH1_MH1") (pintype "passive"))
      (node (ref "J9") (pin "MH2") (pinfunction "MH2_MH2") (pintype "passive"))
      (node (ref "LED1") (pin "1") (pinfunction "K_1") (pintype "passive"))
      (node (ref "R10") (pin "2") (pinfunction "2_2") (pintype "passive"))
      (node (ref "R11") (pin "2") (pinfunction "2_2") (pintype "passive"))
      (node (ref "R17") (pin "1") (pinfunction "1_1") (pintype "passive"))
      (node (ref "R18") (pin "1") (pinfunction "1_1") (pintype "passive"))
      (node (ref "U1") (pin "C") (pinfunction "C_C") (pintype "passive"))
      (node (ref "U1") (pin "MH1") (pinfunction "MH1_MH1") (pintype "passive"))
      (node (ref "U1") (pin "MH2") (pinfunction "MH2_MH2") (pintype "passive"))
      (node (ref "U1") (pin "MH4") (pinfunction "BTN_MH4") (pintype "passive"))
      (node (ref "Y1") (pin "2") (pinfunction "GND_2") (pintype "passive"))
      (node (ref "Y1") (pin "4") (pinfunction "GND_4") (pintype "passive"))
      (node (ref "Y3") (pin "2") (pinfunction "NC_2") (pintype "passive"))
      (node (ref "Y3") (pin "3") (pinfunction "NC_3") (pintype "passive"))
    )
    (net (code "47") (name "Net-(BTN1-SW-Pad2)") (class "Default")
      (node (ref "BTN1") (pin "2") (pinfunction "SW_2") (pintype "passive"))
      (node (ref "J1") (pin "2") (pinfunction "2_2") (pintype "passive"))
    )
    (net (code "48") (name "Net-(IC3-~{MR})") (class "Default")
      (node (ref "IC3") (pin "3") (pinfunction "~{MR}_3") (pintype "passive"))
      (node (ref "J1") (pin "1") (pinfunction "1_1") (pintype "passive"))
    )
    (net (code "49") (name "Net-(IC6-ANT)") (class "Default")
      (node (ref "IC6") (pin "13") (pinfunction "ANT_13") (pintype "passive"))
      (node (ref "J7") (pin "1") (pinfunction "ANT_1") (pintype "passive"))
    )
    (net (code "50") (name "Net-(J6-Pad1)") (class "Default")
      (node (ref "J6") (pin "1") (pinfunction "1_1") (pintype "passive"))
      (node (ref "R7") (pin "1") (pinfunction "1_1") (pintype "passive"))
    )
    (net (code "51") (name "Net-(J6-Pad3)") (class "Default")
      (node (ref "J6") (pin "3") (pinfunction "3_3") (pintype "passive"))
      (node (ref "R8") (pin "1") (pinfunction "1_1") (pintype "passive"))
    )
    (net (code "52") (name "Net-(J6-Pad4)") (class "Default")
      (node (ref "J6") (pin "4") (pinfunction "4_4") (pintype "passive"))
      (node (ref "R9") (pin "1") (pinfunction "1_1") (pintype "passive"))
    )
    (net (code "53") (name "Net-(J6-Pad5)") (class "Default")
      (node (ref "J6") (pin "5") (pinfunction "5_5") (pintype "passive"))
      (node (ref "R12") (pin "1") (pinfunction "1_1") (pintype "passive"))
    )
    (net (code "54") (name "Net-(J6-Pad6)") (class "Default")
      (node (ref "J6") (pin "6") (pinfunction "6_6") (pintype "passive"))
      (node (ref "R13") (pin "1") (pinfunction "1_1") (pintype "passive"))
    )
    (net (code "55") (name "Net-(J6-Pad7)") (class "Default")
      (node (ref "J6") (pin "7") (pinfunction "7_7") (pintype "passive"))
      (node (ref "R14") (pin "1") (pinfunction "1_1") (pintype "passive"))
    )
    (net (code "56") (name "Net-(J8-CC1)") (class "Default")
      (node (ref "J8") (pin "A5") (pinfunction "CC1_A5") (pintype "passive"))
      (node (ref "R18") (pin "2") (pinfunction "2_2") (pintype "passive"))
    )
    (net (code "57") (name "Net-(J8-CC2)") (class "Default")
      (node (ref "J8") (pin "B5") (pinfunction "CC2_B5") (pintype "passive"))
      (node (ref "R17") (pin "2") (pinfunction "2_2") (pintype "passive"))
    )
    (net (code "58") (name "Net-(J9-D+)") (class "Default")
      (node (ref "J9") (pin "3") (pinfunction "D+_3") (pintype "passive"))
      (node (ref "R16") (pin "1") (pinfunction "1_1") (pintype "passive"))
    )
    (net (code "59") (name "Net-(J9-D-)") (class "Default")
      (node (ref "J9") (pin "2") (pinfunction "D-_2") (pintype "passive"))
      (node (ref "R15") (pin "1") (pinfunction "1_1") (pintype "passive"))
    )
    (net (code "60") (name "Net-(LED1-A)") (class "Default")
      (node (ref "LED1") (pin "2") (pinfunction "A_2") (pintype "passive"))
      (node (ref "R3") (pin "1") (pinfunction "1_1") (pintype "passive"))
    )
    (net (code "61") (name "Net-(LED2-A)") (class "Default")
      (node (ref "LED2") (pin "2") (pinfunction "A_2") (pintype "passive"))
      (node (ref "R4") (pin "1") (pinfunction "1_1") (pintype "passive"))
    )
    (net (code "62") (name "Net-(LED3-A)") (class "Default")
      (node (ref "LED3") (pin "2") (pinfunction "A_2") (pintype "passive"))
      (node (ref "R5") (pin "1") (pinfunction "1_1") (pintype "passive"))
    )
    (net (code "63") (name "unconnected-(IC1-GPI0-Pad26)") (class "Default")
      (node (ref "IC1") (pin "26") (pinfunction "GPI0_26") (pintype "passive+no_connect"))
    )
    (net (code "64") (name "unconnected-(IC1-GPI1-Pad27)") (class "Default")
      (node (ref "IC1") (pin "27") (pinfunction "GPI1_27") (pintype "passive+no_connect"))
    )
    (net (code "65") (name "unconnected-(IC1-GPI2-Pad28)") (class "Default")
      (node (ref "IC1") (pin "28") (pinfunction "GPI2_28") (pintype "passive+no_connect"))
    )
    (net (code "66") (name "unconnected-(IC1-GPI3-Pad29)") (class "Default")
      (node (ref "IC1") (pin "29") (pinfunction "GPI3_29") (pintype "passive+no_connect"))
    )
    (net (code "67") (name "unconnected-(IC1-GPI4-Pad30)") (class "Default")
      (node (ref "IC1") (pin "30") (pinfunction "GPI4_30") (pintype "passive+no_connect"))
    )
    (net (code "68") (name "unconnected-(IC1-GPI5-Pad31)") (class "Default")
      (node (ref "IC1") (pin "31") (pinfunction "GPI5_31") (pintype "passive+no_connect"))
    )
    (net (code "69") (name "unconnected-(IC1-GPI6-Pad32)") (class "Default")
      (node (ref "IC1") (pin "32") (pinfunction "GPI6_32") (pintype "passive+no_connect"))
    )
    (net (code "70") (name "unconnected-(IC1-GPI7-Pad1)") (class "Default")
      (node (ref "IC1") (pin "1") (pinfunction "GPI7_1") (pintype "passive+no_connect"))
    )
    (net (code "71") (name "unconnected-(IC1-GPO0-Pad4)") (class "Default")
      (node (ref "IC1") (pin "4") (pinfunction "GPO0_4") (pintype "passive+no_connect"))
    )
    (net (code "72") (name "unconnected-(IC1-GPO1-Pad5)") (class "Default")
      (node (ref "IC1") (pin "5") (pinfunction "GPO1_5") (pintype "passive+no_connect"))
    )
    (net (code "73") (name "unconnected-(IC1-GPO2-Pad6)") (class "Default")
      (node (ref "IC1") (pin "6") (pinfunction "GPO2_6") (pintype "passive+no_connect"))
    )
    (net (code "74") (name "unconnected-(IC1-GPO3-Pad7)") (class "Default")
      (node (ref "IC1") (pin "7") (pinfunction "GPO3_7") (pintype "passive+no_connect"))
    )
    (net (code "75") (name "unconnected-(IC1-GPO4-Pad8)") (class "Default")
      (node (ref "IC1") (pin "8") (pinfunction "GPO4_8") (pintype "passive+no_connect"))
    )
    (net (code "76") (name "unconnected-(IC1-GPO5-Pad9)") (class "Default")
      (node (ref "IC1") (pin "9") (pinfunction "GPO5_9") (pintype "passive+no_connect"))
    )
    (net (code "77") (name "unconnected-(IC1-GPO6-Pad10)") (class "Default")
      (node (ref "IC1") (pin "10") (pinfunction "GPO6_10") (pintype "passive+no_connect"))
    )
    (net (code "78") (name "unconnected-(IC1-GPO7-Pad11)") (class "Default")
      (node (ref "IC1") (pin "11") (pinfunction "GPO7_11") (pintype "passive+no_connect"))
    )
    (net (code "79") (name "unconnected-(IC1-GPX-Pad17)") (class "Default")
      (node (ref "IC1") (pin "17") (pinfunction "GPX_17") (pintype "passive+no_connect"))
    )
    (net (code "80") (name "unconnected-(IC2-PA0-WKUP-Pad10)") (class "Default")
      (node (ref "IC2") (pin "10") (pinfunction "PA0-WKUP_10") (pintype "passive+no_connect"))
    )
    (net (code "81") (name "unconnected-(IC2-PA1-Pad11)") (class "Default")
      (node (ref "IC2") (pin "11") (pinfunction "PA1_11") (pintype "passive+no_connect"))
    )
    (net (code "82") (name "unconnected-(IC2-PA4-Pad14)") (class "Default")
      (node (ref "IC2") (pin "14") (pinfunction "PA4_14") (pintype "passive+no_connect"))
    )
    (net (code "83") (name "unconnected-(IC2-PA11-Pad32)") (class "Default")
      (node (ref "IC2") (pin "32") (pinfunction "PA11_32") (pintype "passive+no_connect"))
    )
    (net (code "84") (name "unconnected-(IC2-PA12-Pad33)") (class "Default")
      (node (ref "IC2") (pin "33") (pinfunction "PA12_33") (pintype "passive+no_connect"))
    )
    (net (code "85") (name "unconnected-(IC2-PC13-TAMPER-RT_C-Pad2)") (class "Default")
      (node (ref "IC2") (pin "2") (pinfunction "PC13-TAMPER-RT_C_2") (pintype "passive+no_connect"))
    )
    (net (code "86") (name "unconnected-(IC4-AIO0-Pad9)") (class "Default")
      (node (ref "IC4") (pin "9") (pinfunction "AIO0_9") (pintype "passive+no_connect"))
    )
    (net (code "87") (name "unconnected-(IC4-AIO1-Pad10)") (class "Default")
      (node (ref "IC4") (pin "10") (pinfunction "AIO1_10") (pintype "passive+no_connect"))
    )
    (net (code "88") (name "unconnected-(IC4-CSB-Pad16)") (class "Default")
      (node (ref "IC4") (pin "16") (pinfunction "CSB_16") (pintype "passive+no_connect"))
    )
    (net (code "89") (name "unconnected-(IC4-CTS-Pad3)") (class "Default")
      (node (ref "IC4") (pin "3") (pinfunction "CTS_3") (pintype "passive+no_connect"))
    )
    (net (code "90") (name "unconnected-(IC4-MISO-Pad18)") (class "Default")
      (node (ref "IC4") (pin "18") (pinfunction "MISO_18") (pintype "passive+no_connect"))
    )
    (net (code "91") (name "unconnected-(IC4-MOSI-Pad17)") (class "Default")
      (node (ref "IC4") (pin "17") (pinfunction "MOSI_17") (pintype "passive+no_connect"))
    )
    (net (code "92") (name "unconnected-(IC4-NC-Pad14)") (class "Default")
      (node (ref "IC4") (pin "14") (pinfunction "NC_14") (pintype "passive+no_connect"))
    )
    (net (code "93") (name "unconnected-(IC4-PCMCLK-Pad5)") (class "Default")
      (node (ref "IC4") (pin "5") (pinfunction "PCMCLK_5") (pintype "passive+no_connect"))
    )
    (net (code "94") (name "unconnected-(IC4-PCMIN-Pad7)") (class "Default")
      (node (ref "IC4") (pin "7") (pinfunction "PCMIN_7") (pintype "passive+no_connect"))
    )
    (net (code "95") (name "unconnected-(IC4-PCMOUT-Pad6)") (class "Default")
      (node (ref "IC4") (pin "6") (pinfunction "PCMOUT_6") (pintype "passive+no_connect"))
    )
    (net (code "96") (name "unconnected-(IC4-PCMSYNC-Pad8)") (class "Default")
      (node (ref "IC4") (pin "8") (pinfunction "PCMSYNC_8") (pintype "passive+no_connect"))
    )
    (net (code "97") (name "unconnected-(IC4-PIO0-Pad23)") (class "Default")
      (node (ref "IC4") (pin "23") (pinfunction "PIO0_23") (pintype "passive+no_connect"))
    )
    (net (code "98") (name "unconnected-(IC4-PIO1-Pad24)") (class "Default")
      (node (ref "IC4") (pin "24") (pinfunction "PIO1_24") (pintype "passive+no_connect"))
    )
    (net (code "99") (name "unconnected-(IC4-PIO2-Pad25)") (class "Default")
      (node (ref "IC4") (pin "25") (pinfunction "PIO2_25") (pintype "passive+no_connect"))
    )
    (net (code "100") (name "unconnected-(IC4-PIO3-Pad26)") (class "Default")
      (node (ref "IC4") (pin "26") (pinfunction "PIO3_26") (pintype "passive+no_connect"))
    )
    (net (code "101") (name "unconnected-(IC4-PIO4-Pad27)") (class "Default")
      (node (ref "IC4") (pin "27") (pinfunction "PIO4_27") (pintype "passive+no_connect"))
    )
    (net (code "102") (name "unconnected-(IC4-PIO5-Pad28)") (class "Default")
      (node (ref "IC4") (pin "28") (pinfunction "PIO5_28") (pintype "passive+no_connect"))
    )
    (net (code "103") (name "unconnected-(IC4-PIO6-Pad29)") (class "Default")
      (node (ref "IC4") (pin "29") (pinfunction "PIO6_29") (pintype "passive+no_connect"))
    )
    (net (code "104") (name "unconnected-(IC4-PIO7-Pad30)") (class "Default")
      (node (ref "IC4") (pin "30") (pinfunction "PIO7_30") (pintype "passive+no_connect"))
    )
    (net (code "105") (name "unconnected-(IC4-PIO9-Pad32)") (class "Default")
      (node (ref "IC4") (pin "32") (pinfunction "PIO9_32") (pintype "passive+no_connect"))
    )
    (net (code "106") (name "unconnected-(IC4-PIO10-Pad33)") (class "Default")
      (node (ref "IC4") (pin "33") (pinfunction "PIO10_33") (pintype "passive+no_connect"))
    )
    (net (code "107") (name "unconnected-(IC4-RTS-Pad4)") (class "Default")
      (node (ref "IC4") (pin "4") (pinfunction "RTS_4") (pintype "passive+no_connect"))
    )
    (net (code "108") (name "unconnected-(IC4-SCLK-Pad19)") (class "Default")
      (node (ref "IC4") (pin "19") (pinfunction "SCLK_19") (pintype "passive+no_connect"))
    )
    (net (code "109") (name "unconnected-(IC4-USBD+-Pad20)") (class "Default")
      (node (ref "IC4") (pin "20") (pinfunction "USBD+_20") (pintype "passive+no_connect"))
    )
    (net (code "110") (name "unconnected-(IC4-USBD--Pad15)") (class "Default")
      (node (ref "IC4") (pin "15") (pinfunction "USBD-_15") (pintype "passive+no_connect"))
    )
    (net (code "111") (name "unconnected-(IC5-3V3OUT-Pad17)") (class "Default")
      (node (ref "IC5") (pin "17") (pinfunction "3V3OUT_17") (pintype "passive+no_connect"))
    )
    (net (code "112") (name "unconnected-(IC5-CBUS2-Pad13)") (class "Default")
      (node (ref "IC5") (pin "13") (pinfunction "CBUS2_13") (pintype "passive+no_connect"))
    )
    (net (code "113") (name "unconnected-(IC5-CBUS3-Pad14)") (class "Default")
      (node (ref "IC5") (pin "14") (pinfunction "CBUS3_14") (pintype "passive+no_connect"))
    )
    (net (code "114") (name "unconnected-(IC5-CBUS4-Pad12)") (class "Default")
      (node (ref "IC5") (pin "12") (pinfunction "CBUS4_12") (pintype "passive+no_connect"))
    )
    (net (code "115") (name "unconnected-(IC5-CTS#-Pad11)") (class "Default")
      (node (ref "IC5") (pin "11") (pinfunction "CTS#_11") (pintype "passive+no_connect"))
    )
    (net (code "116") (name "unconnected-(IC5-DCD#-Pad10)") (class "Default")
      (node (ref "IC5") (pin "10") (pinfunction "DCD#_10") (pintype "passive+no_connect"))
    )
    (net (code "117") (name "unconnected-(IC5-DSR#-Pad9)") (class "Default")
      (node (ref "IC5") (pin "9") (pinfunction "DSR#_9") (pintype "passive+no_connect"))
    )
    (net (code "118") (name "unconnected-(IC5-DTR#-Pad2)") (class "Default")
      (node (ref "IC5") (pin "2") (pinfunction "DTR#_2") (pintype "passive+no_connect"))
    )
    (net (code "119") (name "unconnected-(IC5-NC_1-Pad8)") (class "Default")
      (node (ref "IC5") (pin "8") (pinfunction "NC_1_8") (pintype "passive+no_connect"))
    )
    (net (code "120") (name "unconnected-(IC5-NC_2-Pad24)") (class "Default")
      (node (ref "IC5") (pin "24") (pinfunction "NC_2_24") (pintype "passive+no_connect"))
    )
    (net (code "121") (name "unconnected-(IC5-OSCI-Pad27)") (class "Default")
      (node (ref "IC5") (pin "27") (pinfunction "OSCI_27") (pintype "passive+no_connect"))
    )
    (net (code "122") (name "unconnected-(IC5-OSCO-Pad28)") (class "Default")
      (node (ref "IC5") (pin "28") (pinfunction "OSCO_28") (pintype "passive+no_connect"))
    )
    (net (code "123") (name "unconnected-(IC5-RESET#-Pad19)") (class "Default")
      (node (ref "IC5") (pin "19") (pinfunction "RESET#_19") (pintype "passive+no_connect"))
    )
    (net (code "124") (name "unconnected-(IC5-RI#-Pad6)") (class "Default")
      (node (ref "IC5") (pin "6") (pinfunction "RI#_6") (pintype "passive+no_connect"))
    )
    (net (code "125") (name "unconnected-(IC5-RTS#-Pad3)") (class "Default")
      (node (ref "IC5") (pin "3") (pinfunction "RTS#_3") (pintype "passive+no_connect"))
    )
    (net (code "126") (name "unconnected-(IC6-DIO1-Pad2)") (class "Default")
      (node (ref "IC6") (pin "2") (pinfunction "DIO1_2") (pintype "passive+no_connect"))
    )
    (net (code "127") (name "unconnected-(IC6-DIO2-Pad3)") (class "Default")
      (node (ref "IC6") (pin "3") (pinfunction "DIO2_3") (pintype "passive+no_connect"))
    )
    (net (code "128") (name "unconnected-(IC6-DIO3-Pad4)") (class "Default")
      (node (ref "IC6") (pin "4") (pinfunction "DIO3_4") (pintype "passive+no_connect"))
    )
    (net (code "129") (name "unconnected-(J8-SBU1-PadA8)") (class "Default")
      (node (ref "J8") (pin "A8") (pinfunction "SBU1_A8") (pintype "passive+no_connect"))
    )
    (net (code "130") (name "unconnected-(J8-SBU2-PadB8)") (class "Default")
      (node (ref "J8") (pin "B8") (pinfunction "SBU2_B8") (pintype "passive+no_connect"))
    )
  )
)
